# DAC_PCM5102A.net
KiCad netlist of a schematic drawn in Altium Designer
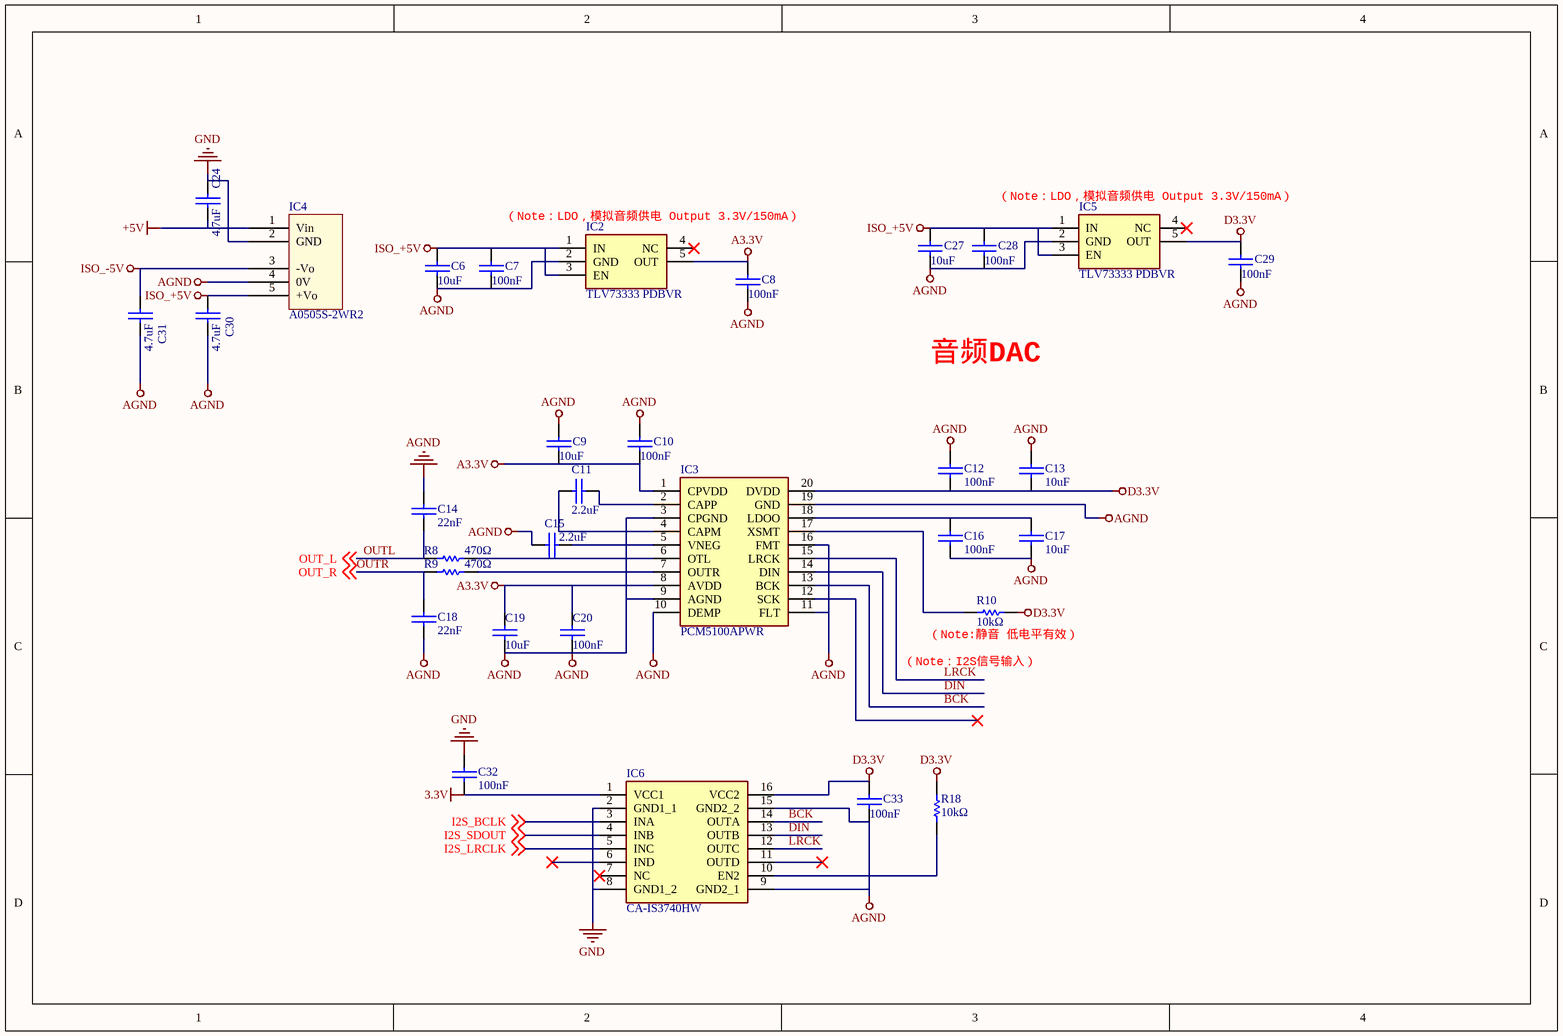
[diagram p0: DAC PCM5102A.SchDoc]

(export (version "E")
  (design (tool "Eeschema 10.0.6"))
  (components
    (comp (ref "C6")
      (value "10uF")
      (footprint "C_0603")
      (description "贴片电容")
      (libsource (lib "IntLib-Passive") (part "Cap_Chip"))
    )
    (comp (ref "C7")
      (value "100nF")
      (footprint "C_0402")
      (description "贴片电容")
      (libsource (lib "IntLib-Passive") (part "Cap_Chip"))
    )
    (comp (ref "C8")
      (value "100nF")
      (footprint "C_0402")
      (description "贴片电容")
      (libsource (lib "IntLib-Passive") (part "Cap_Chip"))
    )
    (comp (ref "C9")
      (value "10uF")
      (footprint "C_0603")
      (description "贴片电容")
      (libsource (lib "IntLib-Passive") (part "Cap_Chip"))
    )
    (comp (ref "C10")
      (value "100nF")
      (footprint "C_0402")
      (description "贴片电容")
      (libsource (lib "IntLib-Passive") (part "Cap_Chip"))
    )
    (comp (ref "C11")
      (value "2.2uF")
      (footprint "C_0402")
      (description "贴片电容")
      (libsource (lib "IntLib-Passive") (part "Cap_Chip"))
    )
    (comp (ref "C12")
      (value "100nF")
      (footprint "C_0402")
      (description "贴片电容")
      (libsource (lib "IntLib-Passive") (part "Cap_Chip"))
    )
    (comp (ref "C13")
      (value "10uF")
      (footprint "C_0603")
      (description "贴片电容")
      (libsource (lib "IntLib-Passive") (part "Cap_Chip"))
    )
    (comp (ref "C14")
      (value "22nF")
      (footprint "C_0402")
      (description "贴片电容")
      (libsource (lib "IntLib-Passive") (part "Cap_Chip"))
    )
    (comp (ref "C15")
      (value "2.2uF")
      (footprint "C_0402")
      (description "贴片电容")
      (libsource (lib "IntLib-Passive") (part "Cap_Chip"))
    )
    (comp (ref "C16")
      (value "100nF")
      (footprint "C_0402")
      (description "贴片电容")
      (libsource (lib "IntLib-Passive") (part "Cap_Chip"))
    )
    (comp (ref "C17")
      (value "10uF")
      (footprint "C_0603")
      (description "贴片电容")
      (libsource (lib "IntLib-Passive") (part "Cap_Chip"))
    )
    (comp (ref "C18")
      (value "22nF")
      (footprint "C_0402")
      (description "贴片电容")
      (libsource (lib "IntLib-Passive") (part "Cap_Chip"))
    )
    (comp (ref "C19")
      (value "10uF")
      (footprint "C_0603")
      (description "贴片电容")
      (libsource (lib "IntLib-Passive") (part "Cap_Chip"))
    )
    (comp (ref "C20")
      (value "100nF")
      (footprint "C_0402")
      (description "贴片电容")
      (libsource (lib "IntLib-Passive") (part "Cap_Chip"))
    )
    (comp (ref "C24")
      (value "4.7uF")
      (footprint "C_0603")
      (description "贴片电容")
      (libsource (lib "IntLib-Passive") (part "Cap_Chip"))
    )
    (comp (ref "C27")
      (value "10uF")
      (footprint "C_0603")
      (description "贴片电容")
      (libsource (lib "IntLib-Passive") (part "Cap_Chip"))
    )
    (comp (ref "C28")
      (value "100nF")
      (footprint "C_0402")
      (description "贴片电容")
      (libsource (lib "IntLib-Passive") (part "Cap_Chip"))
    )
    (comp (ref "C29")
      (value "100nF")
      (footprint "C_0402")
      (description "贴片电容")
      (libsource (lib "IntLib-Passive") (part "Cap_Chip"))
    )
    (comp (ref "C30")
      (value "4.7uF")
      (footprint "C_0603")
      (description "贴片电容")
      (libsource (lib "IntLib-Passive") (part "Cap_Chip"))
    )
    (comp (ref "C31")
      (value "4.7uF")
      (footprint "C_0603")
      (description "贴片电容")
      (libsource (lib "IntLib-Passive") (part "Cap_Chip"))
    )
    (comp (ref "C32")
      (value "100nF")
      (footprint "C_0402")
      (description "贴片电容")
      (libsource (lib "IntLib-Passive") (part "Cap_Chip"))
    )
    (comp (ref "C33")
      (value "100nF")
      (footprint "C_0402")
      (description "贴片电容")
      (libsource (lib "IntLib-Passive") (part "Cap_Chip"))
    )
    (comp (ref "IC2")
      (value "TLV73333 PDBVR")
      (footprint "SamacSys:SOT95P280X145-5N")
      (description "LDO电源芯片")
      (fields (field (name "MANUFACTURER_PART_NUMBER") "TLV73333PDBVR"))
      (libsource (lib "*") (part "TLV71333PDBVR"))
    )
    (comp (ref "IC3")
      (value "PCM5100APWR")
      (footprint "SamacSys:SOP65P640X120-20N")
      (description "音频DAC")
      (libsource (lib "*") (part "PCM5102APWR"))
    )
    (comp (ref "IC4")
      (value "A0505S-2WR2")
      (footprint "B_S-2WR2")
      (description "隔离DC-DC")
      (libsource (lib "Raspberry Pi Module") (part "B_S-2WR2"))
    )
    (comp (ref "IC5")
      (value "TLV73333 PDBVR")
      (footprint "SamacSys:SOT95P280X145-5N")
      (description "LDO电源芯片")
      (fields (field (name "MANUFACTURER_PART_NUMBER") "TLV73333PDBVR"))
      (libsource (lib "*") (part "TLV71333PDBVR"))
    )
    (comp (ref "IC6")
      (value "CA-IS3740HW")
      (footprint "SamacSys:SOIC127P1030X265-16N")
      (description "IO隔离芯片")
      (libsource (lib "*") (part "ISO7740FDW"))
    )
    (comp (ref "R8")
      (value "470Ω")
      (footprint "R_0402")
      (description "贴片电阻")
      (libsource (lib "IntLib-Passive") (part "Res_Chip"))
    )
    (comp (ref "R9")
      (value "470Ω")
      (footprint "R_0402")
      (description "贴片电阻")
      (libsource (lib "IntLib-Passive") (part "Res_Chip"))
    )
    (comp (ref "R10")
      (value "10kΩ")
      (footprint "R_0402")
      (description "贴片电阻")
      (libsource (lib "IntLib-Passive") (part "Res_Chip"))
    )
    (comp (ref "R18")
      (value "10kΩ")
      (footprint "R_0402")
      (description "贴片电阻")
      (libsource (lib "IntLib-Passive") (part "Res_Chip"))
    )
  )
  (nets
    (net (code "1") (name "+5V") (class "Default")
      (node (ref "C24") (pin "2") (pinfunction "2_2") (pintype "passive"))
      (node (ref "IC4") (pin "1") (pinfunction "Vin_1") (pintype "power_in"))
    )
    (net (code "2") (name "/BCK") (class "Default")
      (node (ref "IC3") (pin "13") (pinfunction "BCK_13") (pintype "passive"))
      (node (ref "IC6") (pin "14") (pinfunction "OUTA_14") (pintype "passive"))
    )
    (net (code "3") (name "/DIN") (class "Default")
      (node (ref "IC3") (pin "14") (pinfunction "DIN_14") (pintype "passive"))
      (node (ref "IC6") (pin "13") (pinfunction "OUTB_13") (pintype "passive"))
    )
    (net (code "4") (name "/LRCK") (class "Default")
      (node (ref "IC3") (pin "15") (pinfunction "LRCK_15") (pintype "passive"))
      (node (ref "IC6") (pin "12") (pinfunction "OUTC_12") (pintype "passive"))
    )
    (net (code "5") (name "3.3V") (class "Default")
      (node (ref "C32") (pin "2") (pinfunction "2_2") (pintype "passive"))
      (node (ref "IC6") (pin "1") (pinfunction "VCC1_1") (pintype "passive"))
    )
    (net (code "6") (name "A3.3V") (class "Default")
      (node (ref "C10") (pin "1") (pinfunction "1_1") (pintype "passive"))
      (node (ref "C19") (pin "2") (pinfunction "2_2") (pintype "passive"))
      (node (ref "C20") (pin "2") (pinfunction "2_2") (pintype "passive"))
      (node (ref "C8") (pin "2") (pinfunction "2_2") (pintype "passive"))
      (node (ref "C9") (pin "1") (pinfunction "1_1") (pintype "passive"))
      (node (ref "IC2") (pin "5") (pinfunction "OUT_5") (pintype "passive"))
      (node (ref "IC3") (pin "1") (pinfunction "CPVDD_1") (pintype "passive"))
      (node (ref "IC3") (pin "8") (pinfunction "AVDD_8") (pintype "passive"))
    )
    (net (code "7") (name "AGND") (class "Default")
      (node (ref "C10") (pin "2") (pinfunction "2_2") (pintype "passive"))
      (node (ref "C12") (pin "2") (pinfunction "2_2") (pintype "passive"))
      (node (ref "C13") (pin "2") (pinfunction "2_2") (pintype "passive"))
      (node (ref "C14") (pin "2") (pinfunction "2_2") (pintype "passive"))
      (node (ref "C15") (pin "2") (pinfunction "2_2") (pintype "passive"))
      (node (ref "C16") (pin "1") (pinfunction "1_1") (pintype "passive"))
      (node (ref "C17") (pin "1") (pinfunction "1_1") (pintype "passive"))
      (node (ref "C18") (pin "1") (pinfunction "1_1") (pintype "passive"))
      (node (ref "C19") (pin "1") (pinfunction "1_1") (pintype "passive"))
      (node (ref "C20") (pin "1") (pinfunction "1_1") (pintype "passive"))
      (node (ref "C27") (pin "1") (pinfunction "1_1") (pintype "passive"))
      (node (ref "C28") (pin "1") (pinfunction "1_1") (pintype "passive"))
      (node (ref "C29") (pin "1") (pinfunction "1_1") (pintype "passive"))
      (node (ref "C30") (pin "2") (pinfunction "2_2") (pintype "passive"))
      (node (ref "C31") (pin "2") (pinfunction "2_2") (pintype "passive"))
      (node (ref "C33") (pin "1") (pinfunction "1_1") (pintype "passive"))
      (node (ref "C6") (pin "1") (pinfunction "1_1") (pintype "passive"))
      (node (ref "C7") (pin "1") (pinfunction "1_1") (pintype "passive"))
      (node (ref "C8") (pin "1") (pinfunction "1_1") (pintype "passive"))
      (node (ref "C9") (pin "2") (pinfunction "2_2") (pintype "passive"))
      (node (ref "IC2") (pin "2") (pinfunction "GND_2") (pintype "passive"))
      (node (ref "IC3") (pin "10") (pinfunction "DEMP_10") (pintype "passive"))
      (node (ref "IC3") (pin "11") (pinfunction "FLT_11") (pintype "passive"))
      (node (ref "IC3") (pin "16") (pinfunction "FMT_16") (pintype "passive"))
      (node (ref "IC3") (pin "19") (pinfunction "GND_19") (pintype "passive"))
      (node (ref "IC3") (pin "3") (pinfunction "CPGND_3") (pintype "passive"))
      (node (ref "IC3") (pin "9") (pinfunction "AGND_9") (pintype "passive"))
      (node (ref "IC4") (pin "4") (pinfunction "0V_4") (pintype "power_in"))
      (node (ref "IC5") (pin "2") (pinfunction "GND_2") (pintype "passive"))
      (node (ref "IC6") (pin "15") (pinfunction "GND2_2_15") (pintype "passive"))
      (node (ref "IC6") (pin "9") (pinfunction "GND2_1_9") (pintype "passive"))
    )
    (net (code "8") (name "D3.3V") (class "Default")
      (node (ref "C12") (pin "1") (pinfunction "1_1") (pintype "passive"))
      (node (ref "C13") (pin "1") (pinfunction "1_1") (pintype "passive"))
      (node (ref "C29") (pin "2") (pinfunction "2_2") (pintype "passive"))
      (node (ref "C33") (pin "2") (pinfunction "2_2") (pintype "passive"))
      (node (ref "IC3") (pin "20") (pinfunction "DVDD_20") (pintype "passive"))
      (node (ref "IC5") (pin "5") (pinfunction "OUT_5") (pintype "passive"))
      (node (ref "IC6") (pin "16") (pinfunction "VCC2_16") (pintype "passive"))
      (node (ref "R10") (pin "1") (pinfunction "1_1") (pintype "passive"))
      (node (ref "R18") (pin "1") (pinfunction "1_1") (pintype "passive"))
    )
    (net (code "9") (name "GND") (class "Default")
      (node (ref "C24") (pin "1") (pinfunction "1_1") (pintype "passive"))
      (node (ref "C32") (pin "1") (pinfunction "1_1") (pintype "passive"))
      (node (ref "IC4") (pin "2") (pinfunction "GND_2") (pintype "power_in"))
      (node (ref "IC6") (pin "2") (pinfunction "GND1_1_2") (pintype "passive"))
      (node (ref "IC6") (pin "8") (pinfunction "GND1_2_8") (pintype "passive"))
    )
    (net (code "10") (name "I2S_BCLK") (class "Default")
      (node (ref "IC6") (pin "3") (pinfunction "INA_3") (pintype "passive"))
    )
    (net (code "11") (name "I2S_LRCLK") (class "Default")
      (node (ref "IC6") (pin "5") (pinfunction "INC_5") (pintype "passive"))
    )
    (net (code "12") (name "I2S_SDOUT") (class "Default")
      (node (ref "IC6") (pin "4") (pinfunction "INB_4") (pintype "passive"))
    )
    (net (code "13") (name "ISO_+5V") (class "Default")
      (node (ref "C27") (pin "2") (pinfunction "2_2") (pintype "passive"))
      (node (ref "C28") (pin "2") (pinfunction "2_2") (pintype "passive"))
      (node (ref "C30") (pin "1") (pinfunction "1_1") (pintype "passive"))
      (node (ref "C6") (pin "2") (pinfunction "2_2") (pintype "passive"))
      (node (ref "C7") (pin "2") (pinfunction "2_2") (pintype "passive"))
      (node (ref "IC2") (pin "1") (pinfunction "IN_1") (pintype "passive"))
      (node (ref "IC2") (pin "3") (pinfunction "EN_3") (pintype "passive"))
      (node (ref "IC4") (pin "5") (pinfunction "+Vo_5") (pintype "power_in"))
      (node (ref "IC5") (pin "1") (pinfunction "IN_1") (pintype "passive"))
      (node (ref "IC5") (pin "3") (pinfunction "EN_3") (pintype "passive"))
    )
    (net (code "14") (name "ISO_-5V") (class "Default")
      (node (ref "C31") (pin "1") (pinfunction "1_1") (pintype "passive"))
      (node (ref "IC4") (pin "3") (pinfunction "-Vo_3") (pintype "power_in"))
    )
    (net (code "15") (name "Net-(IC3-CAPM)") (class "Default")
      (node (ref "C11") (pin "2") (pinfunction "2_2") (pintype "passive"))
      (node (ref "IC3") (pin "4") (pinfunction "CAPM_4") (pintype "passive"))
    )
    (net (code "16") (name "Net-(IC3-CAPP)") (class "Default")
      (node (ref "C11") (pin "1") (pinfunction "1_1") (pintype "passive"))
      (node (ref "IC3") (pin "2") (pinfunction "CAPP_2") (pintype "passive"))
    )
    (net (code "17") (name "Net-(IC3-LDOO)") (class "Default")
      (node (ref "C16") (pin "2") (pinfunction "2_2") (pintype "passive"))
      (node (ref "C17") (pin "2") (pinfunction "2_2") (pintype "passive"))
      (node (ref "IC3") (pin "18") (pinfunction "LDOO_18") (pintype "passive"))
    )
    (net (code "18") (name "Net-(IC3-OTL)") (class "Default")
      (node (ref "IC3") (pin "6") (pinfunction "OTL_6") (pintype "passive"))
      (node (ref "R8") (pin "1") (pinfunction "1_1") (pintype "passive"))
    )
    (net (code "19") (name "Net-(IC3-OUTR)") (class "Default")
      (node (ref "IC3") (pin "7") (pinfunction "OUTR_7") (pintype "passive"))
      (node (ref "R9") (pin "1") (pinfunction "1_1") (pintype "passive"))
    )
    (net (code "20") (name "Net-(IC3-VNEG)") (class "Default")
      (node (ref "C15") (pin "1") (pinfunction "1_1") (pintype "passive"))
      (node (ref "IC3") (pin "5") (pinfunction "VNEG_5") (pintype "passive"))
    )
    (net (code "21") (name "Net-(IC3-XSMT)") (class "Default")
      (node (ref "IC3") (pin "17") (pinfunction "XSMT_17") (pintype "passive"))
      (node (ref "R10") (pin "2") (pinfunction "2_2") (pintype "passive"))
    )
    (net (code "22") (name "Net-(IC6-EN2)") (class "Default")
      (node (ref "IC6") (pin "10") (pinfunction "EN2_10") (pintype "passive"))
      (node (ref "R18") (pin "2") (pinfunction "2_2") (pintype "passive"))
    )
    (net (code "23") (name "OUT_L") (class "Default")
      (node (ref "C14") (pin "1") (pinfunction "1_1") (pintype "passive"))
      (node (ref "R8") (pin "2") (pinfunction "2_2") (pintype "passive"))
    )
    (net (code "24") (name "OUT_R") (class "Default")
      (node (ref "C18") (pin "2") (pinfunction "2_2") (pintype "passive"))
      (node (ref "R9") (pin "2") (pinfunction "2_2") (pintype "passive"))
    )
    (net (code "25") (name "unconnected-(IC2-NC-Pad4)") (class "Default")
      (node (ref "IC2") (pin "4") (pinfunction "NC_4") (pintype "passive+no_connect"))
    )
    (net (code "26") (name "unconnected-(IC3-SCK-Pad12)") (class "Default")
      (node (ref "IC3") (pin "12") (pinfunction "SCK_12") (pintype "passive+no_connect"))
    )
    (net (code "27") (name "unconnected-(IC5-NC-Pad4)") (class "Default")
      (node (ref "IC5") (pin "4") (pinfunction "NC_4") (pintype "passive+no_connect"))
    )
    (net (code "28") (name "unconnected-(IC6-IND-Pad6)") (class "Default")
      (node (ref "IC6") (pin "6") (pinfunction "IND_6") (pintype "passive+no_connect"))
    )
    (net (code "29") (name "unconnected-(IC6-NC-Pad7)") (class "Default")
      (node (ref "IC6") (pin "7") (pinfunction "NC_7") (pintype "passive+no_connect"))
    )
    (net (code "30") (name "unconnected-(IC6-OUTD-Pad11)") (class "Default")
      (node (ref "IC6") (pin "11") (pinfunction "OUTD_11") (pintype "passive+no_connect"))
    )
  )
)
